# ASD2022.net
KiCad netlist of a schematic drawn in EAGLE
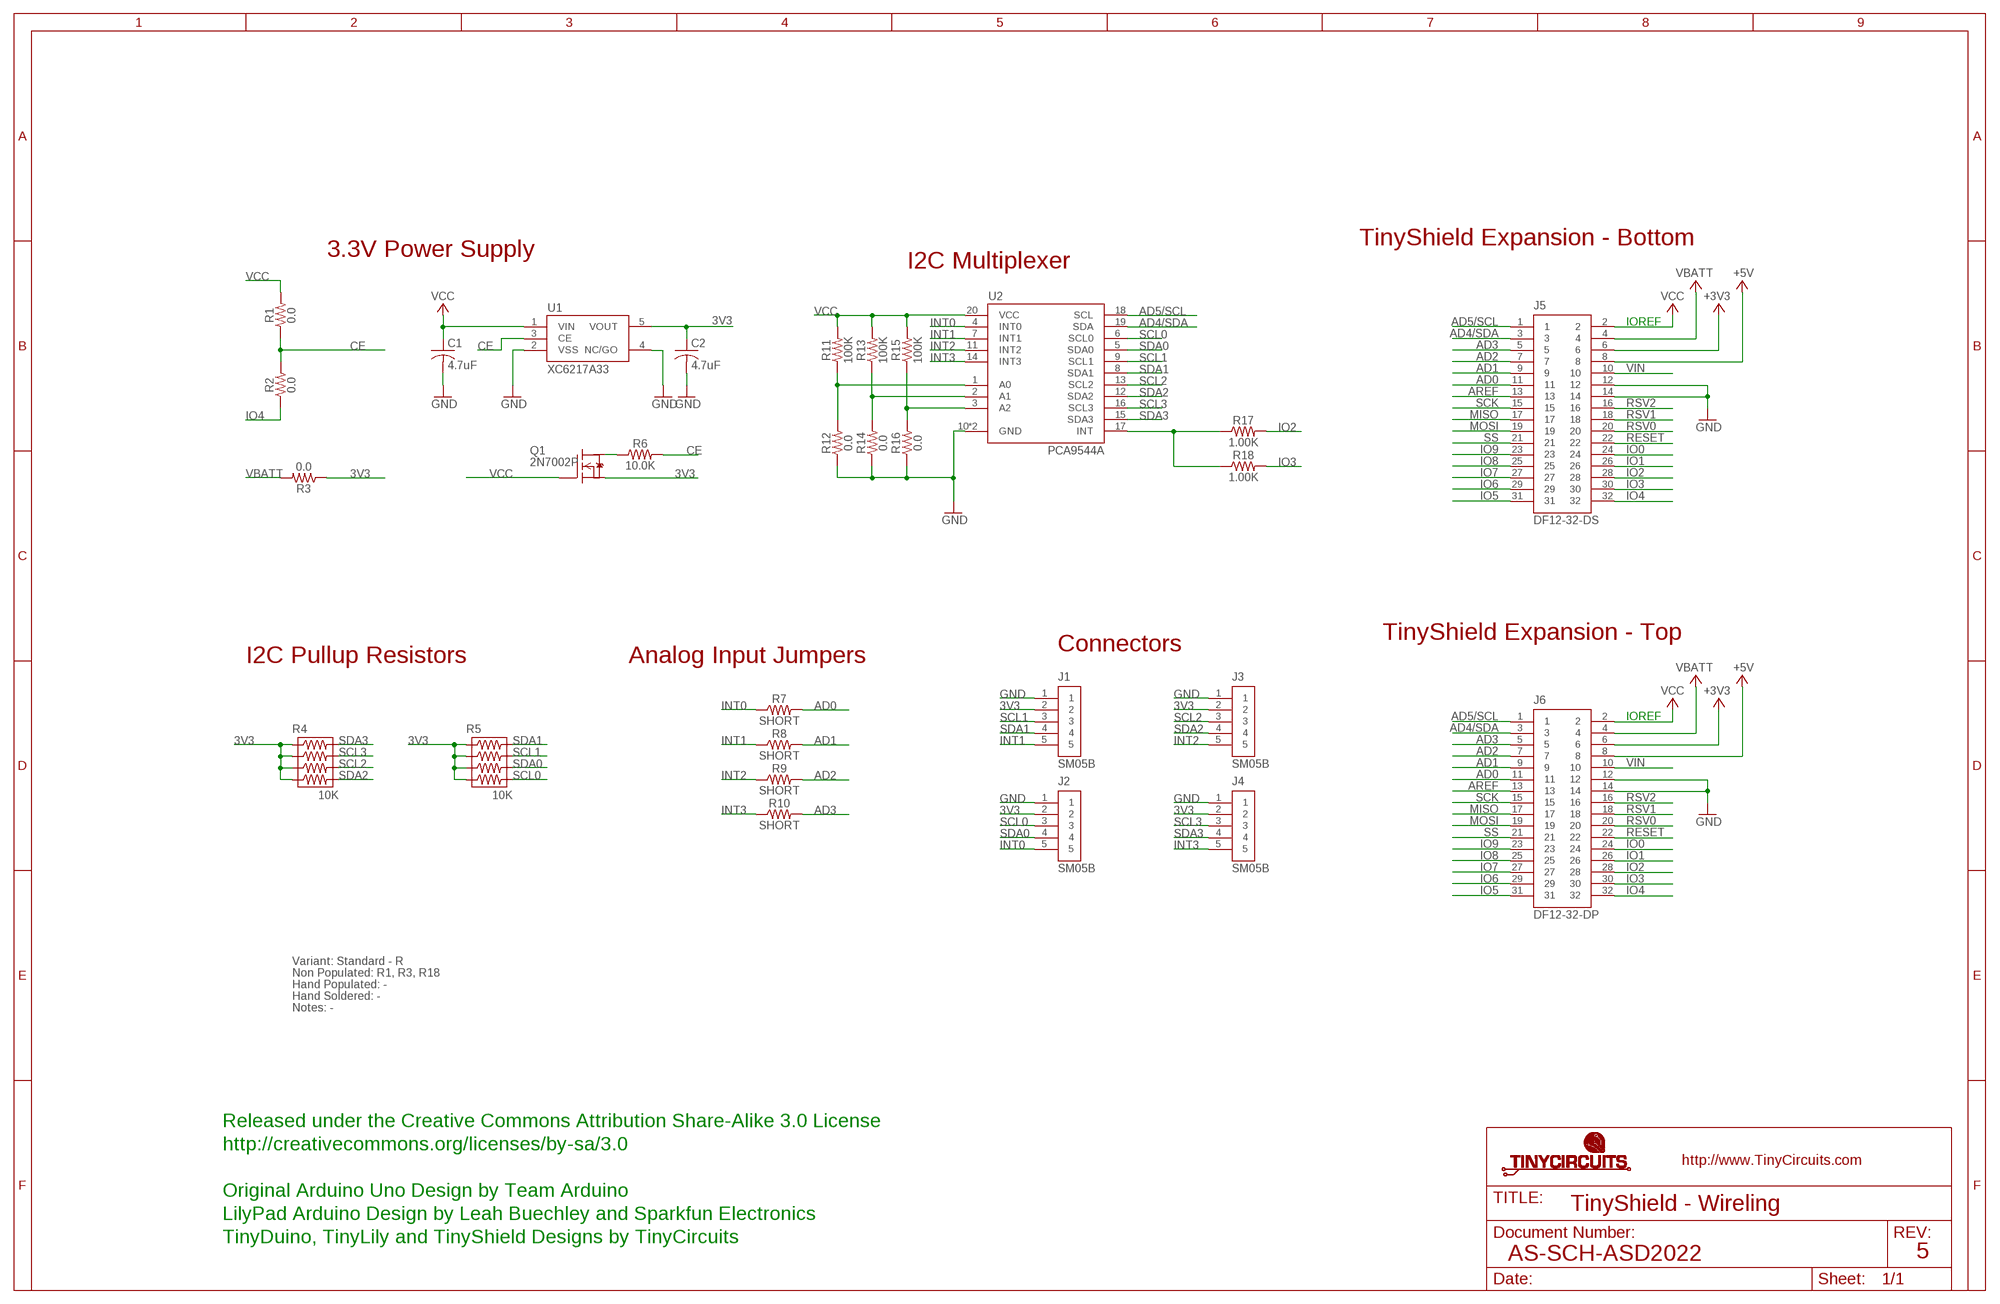
[diagram p0: schematic, sheet 1]

(export (version "E")
  (design (tool "Eeschema 10.0.6"))
  (components
    (comp (ref "C1")
      (value "4.7uF")
      (footprint "eagle-import:C0402")
      (fields (field (name "PARTNO") "AS-ITM-00242") (field (name "PARTNO_1") "AS-ITM-00242"))
      (libsource (lib "eagle-import") (part "AS-ITM-00242"))
    )
    (comp (ref "C2")
      (value "4.7uF")
      (footprint "eagle-import:C0402")
      (fields (field (name "PARTNO") "AS-ITM-00242") (field (name "PARTNO_1") "AS-ITM-00242"))
      (libsource (lib "eagle-import") (part "AS-ITM-00242"))
    )
    (comp (ref "J1")
      (value "SM05B")
      (footprint "eagle-import:JST_SH_5X1_EDGE")
      (fields (field (name "PARTNO") "AS-ITM-00340"))
      (libsource (lib "eagle-import") (part "AS-ITM-00340EDGE"))
    )
    (comp (ref "J2")
      (value "SM05B")
      (footprint "eagle-import:JST_SH_5X1_EDGE")
      (fields (field (name "PARTNO") "AS-ITM-00340"))
      (libsource (lib "eagle-import") (part "AS-ITM-00340EDGE"))
    )
    (comp (ref "J3")
      (value "SM05B")
      (footprint "eagle-import:JST_SH_5X1_EDGE")
      (fields (field (name "PARTNO") "AS-ITM-00340"))
      (libsource (lib "eagle-import") (part "AS-ITM-00340EDGE"))
    )
    (comp (ref "J4")
      (value "SM05B")
      (footprint "eagle-import:JST_SH_5X1_EDGE")
      (fields (field (name "PARTNO") "AS-ITM-00340"))
      (libsource (lib "eagle-import") (part "AS-ITM-00340EDGE"))
    )
    (comp (ref "J5")
      (value "DF12-32-DS")
      (footprint "eagle-import:DF12-32-DS")
      (fields (field (name "PARTNO") "AS-ITM-00012") (field (name "PARTNO_1") "AS-ITM-00012"))
      (libsource (lib "eagle-import") (part "AS-ITM-00012"))
    )
    (comp (ref "J6")
      (value "DF12-32-DP")
      (footprint "eagle-import:DF12-32-DP")
      (fields (field (name "PARTNO") "AS-ITM-00015") (field (name "PARTNO_1") "AS-ITM-00015"))
      (libsource (lib "eagle-import") (part "AS-ITM-00015"))
    )
    (comp (ref "Q1")
      (value "2N7002P")
      (footprint "eagle-import:SOT-416")
      (fields (field (name "PARTNO") "AS-ITM-00110") (field (name "PARTNO_1") "AS-ITM-00110"))
      (libsource (lib "eagle-import") (part "AS-ITM-00110"))
    )
    (comp (ref "R1")
      (value "0.0")
      (footprint "eagle-import:0402")
      (fields (field (name "PARTNO") "AS-ITM-00076") (field (name "PARTNO_1") "AS-ITM-00076"))
      (libsource (lib "eagle-import") (part "AS-ITM-00076"))
    )
    (comp (ref "R2")
      (value "0.0")
      (footprint "eagle-import:0402")
      (fields (field (name "PARTNO") "AS-ITM-00076") (field (name "PARTNO_1") "AS-ITM-00076"))
      (libsource (lib "eagle-import") (part "AS-ITM-00076"))
    )
    (comp (ref "R3")
      (value "0.0")
      (footprint "eagle-import:0402")
      (fields (field (name "PARTNO") "AS-ITM-00076") (field (name "PARTNO_1") "AS-ITM-00076"))
      (libsource (lib "eagle-import") (part "AS-ITM-00076"))
    )
    (comp (ref "R4")
      (value "10K")
      (footprint "eagle-import:0402RPACK")
      (fields (field (name "PARTNO") "AS-ITM-00520") (field (name "PARTNO_1") "AS-ITM-00520"))
      (libsource (lib "eagle-import") (part "AS-ITM-00520"))
    )
    (comp (ref "R5")
      (value "10K")
      (footprint "eagle-import:0402RPACK")
      (fields (field (name "PARTNO") "AS-ITM-00520") (field (name "PARTNO_1") "AS-ITM-00520"))
      (libsource (lib "eagle-import") (part "AS-ITM-00520"))
    )
    (comp (ref "R6")
      (value "10.0K")
      (footprint "eagle-import:0402")
      (fields (field (name "PARTNO") "AS-ITM-00032") (field (name "PARTNO_1") "AS-ITM-00032"))
      (libsource (lib "eagle-import") (part "AS-ITM-00032"))
    )
    (comp (ref "R7")
      (value "SHORT")
      (footprint "eagle-import:0402_SHORT")
      (fields (field (name "PARTNO") "AS-ITM-00076"))
      (libsource (lib "eagle-import") (part "AS-ITM-000760402_SHORT"))
    )
    (comp (ref "R8")
      (value "SHORT")
      (footprint "eagle-import:0402_SHORT")
      (fields (field (name "PARTNO") "AS-ITM-00076"))
      (libsource (lib "eagle-import") (part "AS-ITM-000760402_SHORT"))
    )
    (comp (ref "R9")
      (value "SHORT")
      (footprint "eagle-import:0402_SHORT")
      (fields (field (name "PARTNO") "AS-ITM-00076"))
      (libsource (lib "eagle-import") (part "AS-ITM-000760402_SHORT"))
    )
    (comp (ref "R10")
      (value "SHORT")
      (footprint "eagle-import:0402_SHORT")
      (fields (field (name "PARTNO") "AS-ITM-00076"))
      (libsource (lib "eagle-import") (part "AS-ITM-000760402_SHORT"))
    )
    (comp (ref "R11")
      (value "100K")
      (footprint "eagle-import:0402")
      (fields (field (name "PARTNO") "AS-ITM-00004") (field (name "PARTNO_1") "AS-ITM-00004"))
      (libsource (lib "eagle-import") (part "AS-ITM-00004"))
    )
    (comp (ref "R12")
      (value "0.0")
      (footprint "eagle-import:0402")
      (fields (field (name "PARTNO") "AS-ITM-00076") (field (name "PARTNO_1") "AS-ITM-00076"))
      (libsource (lib "eagle-import") (part "AS-ITM-00076"))
    )
    (comp (ref "R13")
      (value "100K")
      (footprint "eagle-import:0402")
      (fields (field (name "PARTNO") "AS-ITM-00004") (field (name "PARTNO_1") "AS-ITM-00004"))
      (libsource (lib "eagle-import") (part "AS-ITM-00004"))
    )
    (comp (ref "R14")
      (value "0.0")
      (footprint "eagle-import:0402")
      (fields (field (name "PARTNO") "AS-ITM-00076") (field (name "PARTNO_1") "AS-ITM-00076"))
      (libsource (lib "eagle-import") (part "AS-ITM-00076"))
    )
    (comp (ref "R15")
      (value "100K")
      (footprint "eagle-import:0402")
      (fields (field (name "PARTNO") "AS-ITM-00004") (field (name "PARTNO_1") "AS-ITM-00004"))
      (libsource (lib "eagle-import") (part "AS-ITM-00004"))
    )
    (comp (ref "R16")
      (value "0.0")
      (footprint "eagle-import:0402")
      (fields (field (name "PARTNO") "AS-ITM-00076") (field (name "PARTNO_1") "AS-ITM-00076"))
      (libsource (lib "eagle-import") (part "AS-ITM-00076"))
    )
    (comp (ref "R17")
      (value "1.00K")
      (footprint "eagle-import:0402")
      (fields (field (name "PARTNO") "AS-ITM-00003"))
      (libsource (lib "eagle-import") (part "AS-ITM-00003"))
    )
    (comp (ref "R18")
      (value "1.00K")
      (footprint "eagle-import:0402")
      (fields (field (name "PARTNO") "AS-ITM-00003"))
      (libsource (lib "eagle-import") (part "AS-ITM-00003"))
    )
    (comp (ref "U1")
      (value "XC6217A33")
      (footprint "eagle-import:SOT-25")
      (fields (field (name "PARTNO") "AS-ITM-00249") (field (name "PARTNO_1") "AS-ITM-00249"))
      (libsource (lib "eagle-import") (part "AS-ITM-00249"))
    )
    (comp (ref "U2")
      (value "PCA9544A")
      (footprint "eagle-import:VQFN-20_4.5X3.5")
      (fields (field (name "PARTNO") "AS-ITM-00342"))
      (libsource (lib "eagle-import") (part "AS-ITM-00342"))
    )
  )
  (nets
    (net (code "1") (name "+3V3") (class "Default")
      (node (ref "J5") (pin "6") (pinfunction "6_6") (pintype "bidirectional"))
      (node (ref "J6") (pin "6") (pinfunction "6_6") (pintype "bidirectional"))
    )
    (net (code "2") (name "+5V") (class "Default")
      (node (ref "J5") (pin "8") (pinfunction "8_8") (pintype "bidirectional"))
      (node (ref "J6") (pin "8") (pinfunction "8_8") (pintype "bidirectional"))
    )
    (net (code "3") (name "/3V3") (class "Default")
      (node (ref "C2") (pin "1") (pinfunction "1_1") (pintype "passive"))
      (node (ref "J1") (pin "2") (pinfunction "2_2") (pintype "bidirectional"))
      (node (ref "J2") (pin "2") (pinfunction "2_2") (pintype "bidirectional"))
      (node (ref "J3") (pin "2") (pinfunction "2_2") (pintype "bidirectional"))
      (node (ref "J4") (pin "2") (pinfunction "2_2") (pintype "bidirectional"))
      (node (ref "Q1") (pin "2") (pinfunction "S_2") (pintype "passive"))
      (node (ref "R3") (pin "1") (pinfunction "1_1") (pintype "passive"))
      (node (ref "R4") (pin "1") (pinfunction "1_1") (pintype "passive"))
      (node (ref "R4") (pin "3") (pinfunction "3_3") (pintype "passive"))
      (node (ref "R4") (pin "5") (pinfunction "5_5") (pintype "passive"))
      (node (ref "R4") (pin "7") (pinfunction "7_7") (pintype "passive"))
      (node (ref "R5") (pin "1") (pinfunction "1_1") (pintype "passive"))
      (node (ref "R5") (pin "3") (pinfunction "3_3") (pintype "passive"))
      (node (ref "R5") (pin "5") (pinfunction "5_5") (pintype "passive"))
      (node (ref "R5") (pin "7") (pinfunction "7_7") (pintype "passive"))
      (node (ref "U1") (pin "5") (pinfunction "VOUT_5") (pintype "bidirectional"))
    )
    (net (code "4") (name "/AD0") (class "Default")
      (node (ref "J5") (pin "11") (pinfunction "11_11") (pintype "bidirectional"))
      (node (ref "J6") (pin "11") (pinfunction "11_11") (pintype "bidirectional"))
      (node (ref "R7") (pin "2") (pinfunction "2_2") (pintype "passive"))
    )
    (net (code "5") (name "/AD1") (class "Default")
      (node (ref "J5") (pin "9") (pinfunction "9_9") (pintype "bidirectional"))
      (node (ref "J6") (pin "9") (pinfunction "9_9") (pintype "bidirectional"))
      (node (ref "R8") (pin "2") (pinfunction "2_2") (pintype "passive"))
    )
    (net (code "6") (name "/AD2") (class "Default")
      (node (ref "J5") (pin "7") (pinfunction "7_7") (pintype "bidirectional"))
      (node (ref "J6") (pin "7") (pinfunction "7_7") (pintype "bidirectional"))
      (node (ref "R9") (pin "2") (pinfunction "2_2") (pintype "passive"))
    )
    (net (code "7") (name "/AD3") (class "Default")
      (node (ref "J5") (pin "5") (pinfunction "5_5") (pintype "bidirectional"))
      (node (ref "J6") (pin "5") (pinfunction "5_5") (pintype "bidirectional"))
      (node (ref "R10") (pin "2") (pinfunction "2_2") (pintype "passive"))
    )
    (net (code "8") (name "/AD4{slash}SDA") (class "Default")
      (node (ref "J5") (pin "3") (pinfunction "3_3") (pintype "bidirectional"))
      (node (ref "J6") (pin "3") (pinfunction "3_3") (pintype "bidirectional"))
      (node (ref "U2") (pin "19") (pinfunction "SDA_19") (pintype "bidirectional"))
    )
    (net (code "9") (name "/AD5{slash}SCL") (class "Default")
      (node (ref "J5") (pin "1") (pinfunction "1_1") (pintype "bidirectional"))
      (node (ref "J6") (pin "1") (pinfunction "1_1") (pintype "bidirectional"))
      (node (ref "U2") (pin "18") (pinfunction "SCL_18") (pintype "bidirectional"))
    )
    (net (code "10") (name "/AREF") (class "Default")
      (node (ref "J5") (pin "13") (pinfunction "13_13") (pintype "bidirectional"))
      (node (ref "J6") (pin "13") (pinfunction "13_13") (pintype "bidirectional"))
    )
    (net (code "11") (name "/CE") (class "Default")
      (node (ref "R1") (pin "1") (pinfunction "1_1") (pintype "passive"))
      (node (ref "R2") (pin "2") (pinfunction "2_2") (pintype "passive"))
      (node (ref "R6") (pin "2") (pinfunction "2_2") (pintype "passive"))
      (node (ref "U1") (pin "3") (pinfunction "CE_3") (pintype "bidirectional"))
    )
    (net (code "12") (name "/INT0") (class "Default")
      (node (ref "J2") (pin "5") (pinfunction "5_5") (pintype "bidirectional"))
      (node (ref "R7") (pin "1") (pinfunction "1_1") (pintype "passive"))
      (node (ref "U2") (pin "4") (pinfunction "INT0_4") (pintype "bidirectional"))
    )
    (net (code "13") (name "/INT1") (class "Default")
      (node (ref "J1") (pin "5") (pinfunction "5_5") (pintype "bidirectional"))
      (node (ref "R8") (pin "1") (pinfunction "1_1") (pintype "passive"))
      (node (ref "U2") (pin "7") (pinfunction "INT1_7") (pintype "bidirectional"))
    )
    (net (code "14") (name "/INT2") (class "Default")
      (node (ref "J3") (pin "5") (pinfunction "5_5") (pintype "bidirectional"))
      (node (ref "R9") (pin "1") (pinfunction "1_1") (pintype "passive"))
      (node (ref "U2") (pin "11") (pinfunction "INT2_11") (pintype "bidirectional"))
    )
    (net (code "15") (name "/INT3") (class "Default")
      (node (ref "J4") (pin "5") (pinfunction "5_5") (pintype "bidirectional"))
      (node (ref "R10") (pin "1") (pinfunction "1_1") (pintype "passive"))
      (node (ref "U2") (pin "14") (pinfunction "INT3_14") (pintype "bidirectional"))
    )
    (net (code "16") (name "/IO0") (class "Default")
      (node (ref "J5") (pin "24") (pinfunction "24_24") (pintype "bidirectional"))
      (node (ref "J6") (pin "24") (pinfunction "24_24") (pintype "bidirectional"))
    )
    (net (code "17") (name "/IO1") (class "Default")
      (node (ref "J5") (pin "26") (pinfunction "26_26") (pintype "bidirectional"))
      (node (ref "J6") (pin "26") (pinfunction "26_26") (pintype "bidirectional"))
    )
    (net (code "18") (name "/IO2") (class "Default")
      (node (ref "J5") (pin "28") (pinfunction "28_28") (pintype "bidirectional"))
      (node (ref "J6") (pin "28") (pinfunction "28_28") (pintype "bidirectional"))
      (node (ref "R17") (pin "2") (pinfunction "2_2") (pintype "passive"))
    )
    (net (code "19") (name "/IO3") (class "Default")
      (node (ref "J5") (pin "30") (pinfunction "30_30") (pintype "bidirectional"))
      (node (ref "J6") (pin "30") (pinfunction "30_30") (pintype "bidirectional"))
      (node (ref "R18") (pin "2") (pinfunction "2_2") (pintype "passive"))
    )
    (net (code "20") (name "/IO4") (class "Default")
      (node (ref "J5") (pin "32") (pinfunction "32_32") (pintype "bidirectional"))
      (node (ref "J6") (pin "32") (pinfunction "32_32") (pintype "bidirectional"))
      (node (ref "R2") (pin "1") (pinfunction "1_1") (pintype "passive"))
    )
    (net (code "21") (name "/IO5") (class "Default")
      (node (ref "J5") (pin "31") (pinfunction "31_31") (pintype "bidirectional"))
      (node (ref "J6") (pin "31") (pinfunction "31_31") (pintype "bidirectional"))
    )
    (net (code "22") (name "/IO6") (class "Default")
      (node (ref "J5") (pin "29") (pinfunction "29_29") (pintype "bidirectional"))
      (node (ref "J6") (pin "29") (pinfunction "29_29") (pintype "bidirectional"))
    )
    (net (code "23") (name "/IO7") (class "Default")
      (node (ref "J5") (pin "27") (pinfunction "27_27") (pintype "bidirectional"))
      (node (ref "J6") (pin "27") (pinfunction "27_27") (pintype "bidirectional"))
    )
    (net (code "24") (name "/IO8") (class "Default")
      (node (ref "J5") (pin "25") (pinfunction "25_25") (pintype "bidirectional"))
      (node (ref "J6") (pin "25") (pinfunction "25_25") (pintype "bidirectional"))
    )
    (net (code "25") (name "/IO9") (class "Default")
      (node (ref "J5") (pin "23") (pinfunction "23_23") (pintype "bidirectional"))
      (node (ref "J6") (pin "23") (pinfunction "23_23") (pintype "bidirectional"))
    )
    (net (code "26") (name "/MISO") (class "Default")
      (node (ref "J5") (pin "17") (pinfunction "17_17") (pintype "bidirectional"))
      (node (ref "J6") (pin "17") (pinfunction "17_17") (pintype "bidirectional"))
    )
    (net (code "27") (name "/MOSI") (class "Default")
      (node (ref "J5") (pin "19") (pinfunction "19_19") (pintype "bidirectional"))
      (node (ref "J6") (pin "19") (pinfunction "19_19") (pintype "bidirectional"))
    )
    (net (code "28") (name "/RESET") (class "Default")
      (node (ref "J5") (pin "22") (pinfunction "22_22") (pintype "bidirectional"))
      (node (ref "J6") (pin "22") (pinfunction "22_22") (pintype "bidirectional"))
    )
    (net (code "29") (name "/RSV0") (class "Default")
      (node (ref "J5") (pin "20") (pinfunction "20_20") (pintype "bidirectional"))
      (node (ref "J6") (pin "20") (pinfunction "20_20") (pintype "bidirectional"))
    )
    (net (code "30") (name "/RSV1") (class "Default")
      (node (ref "J5") (pin "18") (pinfunction "18_18") (pintype "bidirectional"))
      (node (ref "J6") (pin "18") (pinfunction "18_18") (pintype "bidirectional"))
    )
    (net (code "31") (name "/RSV2") (class "Default")
      (node (ref "J5") (pin "16") (pinfunction "16_16") (pintype "bidirectional"))
      (node (ref "J6") (pin "16") (pinfunction "16_16") (pintype "bidirectional"))
    )
    (net (code "32") (name "/SCK") (class "Default")
      (node (ref "J5") (pin "15") (pinfunction "15_15") (pintype "bidirectional"))
      (node (ref "J6") (pin "15") (pinfunction "15_15") (pintype "bidirectional"))
    )
    (net (code "33") (name "/SCL0") (class "Default")
      (node (ref "J2") (pin "3") (pinfunction "3_3") (pintype "bidirectional"))
      (node (ref "R5") (pin "8") (pinfunction "8_8") (pintype "passive"))
      (node (ref "U2") (pin "6") (pinfunction "SCL0_6") (pintype "bidirectional"))
    )
    (net (code "34") (name "/SCL1") (class "Default")
      (node (ref "J1") (pin "3") (pinfunction "3_3") (pintype "bidirectional"))
      (node (ref "R5") (pin "4") (pinfunction "4_4") (pintype "passive"))
      (node (ref "U2") (pin "9") (pinfunction "SCL1_9") (pintype "bidirectional"))
    )
    (net (code "35") (name "/SCL2") (class "Default")
      (node (ref "J3") (pin "3") (pinfunction "3_3") (pintype "bidirectional"))
      (node (ref "R4") (pin "6") (pinfunction "6_6") (pintype "passive"))
      (node (ref "U2") (pin "13") (pinfunction "SCL2_13") (pintype "bidirectional"))
    )
    (net (code "36") (name "/SCL3") (class "Default")
      (node (ref "J4") (pin "3") (pinfunction "3_3") (pintype "bidirectional"))
      (node (ref "R4") (pin "4") (pinfunction "4_4") (pintype "passive"))
      (node (ref "U2") (pin "16") (pinfunction "SCL3_16") (pintype "bidirectional"))
    )
    (net (code "37") (name "/SDA0") (class "Default")
      (node (ref "J2") (pin "4") (pinfunction "4_4") (pintype "bidirectional"))
      (node (ref "R5") (pin "6") (pinfunction "6_6") (pintype "passive"))
      (node (ref "U2") (pin "5") (pinfunction "SDA0_5") (pintype "bidirectional"))
    )
    (net (code "38") (name "/SDA1") (class "Default")
      (node (ref "J1") (pin "4") (pinfunction "4_4") (pintype "bidirectional"))
      (node (ref "R5") (pin "2") (pinfunction "2_2") (pintype "passive"))
      (node (ref "U2") (pin "8") (pinfunction "SDA1_8") (pintype "bidirectional"))
    )
    (net (code "39") (name "/SDA2") (class "Default")
      (node (ref "J3") (pin "4") (pinfunction "4_4") (pintype "bidirectional"))
      (node (ref "R4") (pin "8") (pinfunction "8_8") (pintype "passive"))
      (node (ref "U2") (pin "12") (pinfunction "SDA2_12") (pintype "bidirectional"))
    )
    (net (code "40") (name "/SDA3") (class "Default")
      (node (ref "J4") (pin "4") (pinfunction "4_4") (pintype "bidirectional"))
      (node (ref "R4") (pin "2") (pinfunction "2_2") (pintype "passive"))
      (node (ref "U2") (pin "15") (pinfunction "SDA3_15") (pintype "bidirectional"))
    )
    (net (code "41") (name "/SS") (class "Default")
      (node (ref "J5") (pin "21") (pinfunction "21_21") (pintype "bidirectional"))
      (node (ref "J6") (pin "21") (pinfunction "21_21") (pintype "bidirectional"))
    )
    (net (code "42") (name "/VIN") (class "Default")
      (node (ref "J5") (pin "10") (pinfunction "10_10") (pintype "bidirectional"))
      (node (ref "J6") (pin "10") (pinfunction "10_10") (pintype "bidirectional"))
    )
    (net (code "43") (name "GND") (class "Default")
      (node (ref "C1") (pin "2") (pinfunction "2_2") (pintype "passive"))
      (node (ref "C2") (pin "2") (pinfunction "2_2") (pintype "passive"))
      (node (ref "J1") (pin "1") (pinfunction "1_1") (pintype "bidirectional"))
      (node (ref "J2") (pin "1") (pinfunction "1_1") (pintype "bidirectional"))
      (node (ref "J3") (pin "1") (pinfunction "1_1") (pintype "bidirectional"))
      (node (ref "J4") (pin "1") (pinfunction "1_1") (pintype "bidirectional"))
      (node (ref "J5") (pin "12") (pinfunction "12_12") (pintype "bidirectional"))
      (node (ref "J5") (pin "14") (pinfunction "14_14") (pintype "bidirectional"))
      (node (ref "J6") (pin "12") (pinfunction "12_12") (pintype "bidirectional"))
      (node (ref "J6") (pin "14") (pinfunction "14_14") (pintype "bidirectional"))
      (node (ref "R12") (pin "1") (pinfunction "1_1") (pintype "passive"))
      (node (ref "R14") (pin "1") (pinfunction "1_1") (pintype "passive"))
      (node (ref "R16") (pin "1") (pinfunction "1_1") (pintype "passive"))
      (node (ref "U1") (pin "2") (pinfunction "VSS_2") (pintype "power_in"))
      (node (ref "U1") (pin "4") (pinfunction "NC/GO_4") (pintype "bidirectional"))
      (node (ref "U2") (pin "10") (pinfunction "GND_10") (pintype "bidirectional"))
      (node (ref "U2") (pin "PAD") (pinfunction "GND_PAD") (pintype "bidirectional"))
    )
    (net (code "44") (name "Net-(Q1-D)") (class "Default")
      (node (ref "Q1") (pin "3") (pinfunction "D_3") (pintype "passive"))
      (node (ref "R6") (pin "1") (pinfunction "1_1") (pintype "passive"))
    )
    (net (code "45") (name "Net-(U2-A0)") (class "Default")
      (node (ref "R11") (pin "1") (pinfunction "1_1") (pintype "passive"))
      (node (ref "R12") (pin "2") (pinfunction "2_2") (pintype "passive"))
      (node (ref "U2") (pin "1") (pinfunction "A0_1") (pintype "bidirectional"))
    )
    (net (code "46") (name "Net-(U2-A1)") (class "Default")
      (node (ref "R13") (pin "1") (pinfunction "1_1") (pintype "passive"))
      (node (ref "R14") (pin "2") (pinfunction "2_2") (pintype "passive"))
      (node (ref "U2") (pin "2") (pinfunction "A1_2") (pintype "bidirectional"))
    )
    (net (code "47") (name "Net-(U2-A2)") (class "Default")
      (node (ref "R15") (pin "1") (pinfunction "1_1") (pintype "passive"))
      (node (ref "R16") (pin "2") (pinfunction "2_2") (pintype "passive"))
      (node (ref "U2") (pin "3") (pinfunction "A2_3") (pintype "bidirectional"))
    )
    (net (code "48") (name "Net-(U2-INT)") (class "Default")
      (node (ref "R17") (pin "1") (pinfunction "1_1") (pintype "passive"))
      (node (ref "R18") (pin "1") (pinfunction "1_1") (pintype "passive"))
      (node (ref "U2") (pin "17") (pinfunction "INT_17") (pintype "bidirectional"))
    )
    (net (code "49") (name "VBATT") (class "Default")
      (node (ref "J5") (pin "4") (pinfunction "4_4") (pintype "bidirectional"))
      (node (ref "J6") (pin "4") (pinfunction "4_4") (pintype "bidirectional"))
      (node (ref "R3") (pin "2") (pinfunction "2_2") (pintype "passive"))
    )
    (net (code "50") (name "VCC") (class "Default")
      (node (ref "C1") (pin "1") (pinfunction "1_1") (pintype "passive"))
      (node (ref "J5") (pin "2") (pinfunction "2_2") (pintype "bidirectional"))
      (node (ref "J6") (pin "2") (pinfunction "2_2") (pintype "bidirectional"))
      (node (ref "Q1") (pin "1") (pinfunction "G_1") (pintype "passive"))
      (node (ref "R1") (pin "2") (pinfunction "2_2") (pintype "passive"))
      (node (ref "R11") (pin "2") (pinfunction "2_2") (pintype "passive"))
      (node (ref "R13") (pin "2") (pinfunction "2_2") (pintype "passive"))
      (node (ref "R15") (pin "2") (pinfunction "2_2") (pintype "passive"))
      (node (ref "U1") (pin "1") (pinfunction "VIN_1") (pintype "bidirectional"))
      (node (ref "U2") (pin "20") (pinfunction "VCC_20") (pintype "bidirectional"))
    )
  )
)
